# Debugger_V1_1.net
KiCad netlist of a schematic drawn in EAGLE
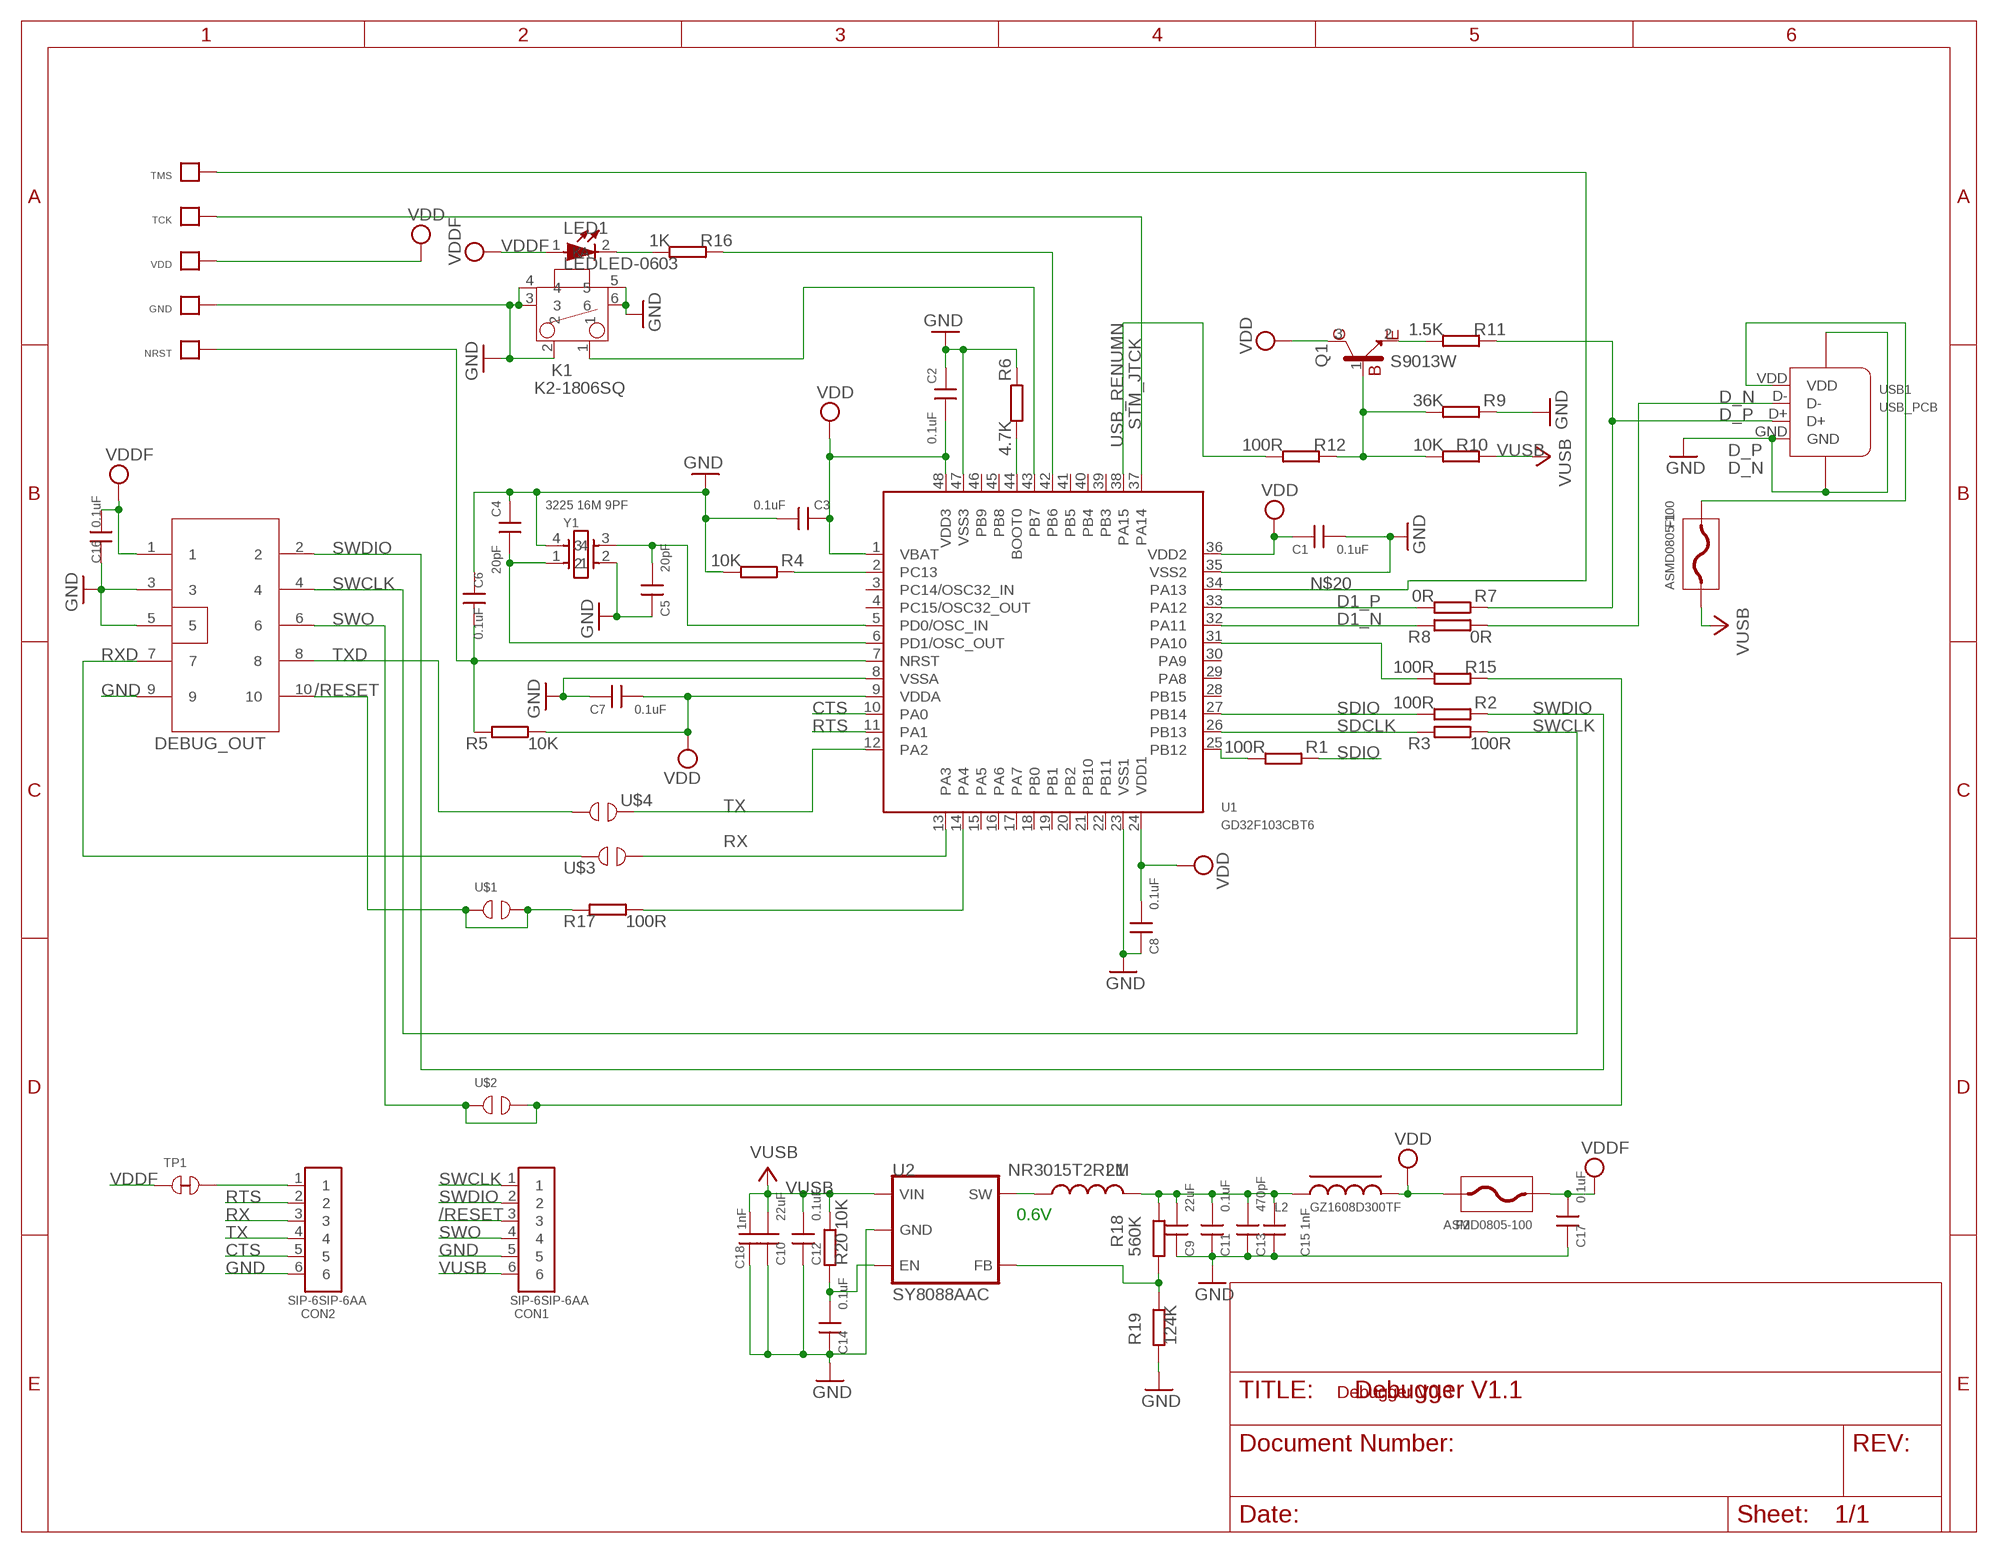
[diagram p0: schematic, sheet 1]

(export (version "E")
  (design (tool "Eeschema 10.0.6"))
  (components
    (comp (ref "C1")
      (value "0.1uF")
      (footprint "eagle-import:C0402")
      (libsource (lib "eagle-import") (part "CAP0402A"))
    )
    (comp (ref "C2")
      (value "0.1uF")
      (footprint "eagle-import:C0402")
      (libsource (lib "eagle-import") (part "CAP0402A"))
    )
    (comp (ref "C3")
      (value "0.1uF")
      (footprint "eagle-import:C0402")
      (libsource (lib "eagle-import") (part "CAP0402A"))
    )
    (comp (ref "C4")
      (value "20pF")
      (footprint "eagle-import:C0402")
      (libsource (lib "eagle-import") (part "CAP0402A"))
    )
    (comp (ref "C5")
      (value "20pF")
      (footprint "eagle-import:C0402")
      (libsource (lib "eagle-import") (part "CAP0402A"))
    )
    (comp (ref "C6")
      (value "0.1uF")
      (footprint "eagle-import:C0402")
      (libsource (lib "eagle-import") (part "CAP0402A"))
    )
    (comp (ref "C7")
      (value "0.1uF")
      (footprint "eagle-import:C0402")
      (libsource (lib "eagle-import") (part "CAP0402A"))
    )
    (comp (ref "C8")
      (value "0.1uF")
      (footprint "eagle-import:C0402")
      (libsource (lib "eagle-import") (part "CAP0402A"))
    )
    (comp (ref "C9")
      (value "22uF")
      (footprint "eagle-import:C0805")
      (libsource (lib "eagle-import") (part "CAPC0805"))
    )
    (comp (ref "C10")
      (value "22uF")
      (footprint "eagle-import:C0805")
      (libsource (lib "eagle-import") (part "CAPC0805"))
    )
    (comp (ref "C11")
      (value "0.1uF")
      (footprint "eagle-import:C0402")
      (libsource (lib "eagle-import") (part "CAP0402A"))
    )
    (comp (ref "C12")
      (value "0.1uF")
      (footprint "eagle-import:C0402")
      (libsource (lib "eagle-import") (part "CAP0402A"))
    )
    (comp (ref "C13")
      (value "470pF")
      (footprint "eagle-import:C0402")
      (libsource (lib "eagle-import") (part "CAP0402A"))
    )
    (comp (ref "C14")
      (value "0.1uF")
      (footprint "eagle-import:C0402")
      (libsource (lib "eagle-import") (part "CAP0402A"))
    )
    (comp (ref "C15")
      (value "1nF")
      (footprint "eagle-import:C0402")
      (libsource (lib "eagle-import") (part "CAP0402A"))
    )
    (comp (ref "C16")
      (value "0.1uF")
      (footprint "eagle-import:C0402")
      (libsource (lib "eagle-import") (part "CAP0402A"))
    )
    (comp (ref "C17")
      (value "0.1uF")
      (footprint "eagle-import:C0402")
      (libsource (lib "eagle-import") (part "CAP0402A"))
    )
    (comp (ref "C18")
      (value "1nF")
      (footprint "eagle-import:C0402")
      (libsource (lib "eagle-import") (part "CAP0402A"))
    )
    (comp (ref "CON1")
      (value "SIP-6SIP-6AA")
      (footprint "eagle-import:PAIZHEN6P_2.54AA")
      (libsource (lib "eagle-import") (part "SIP-6SIP-6AA"))
    )
    (comp (ref "CON2")
      (value "SIP-6SIP-6AA")
      (footprint "eagle-import:PAIZHEN6P_2.54AA")
      (libsource (lib "eagle-import") (part "SIP-6SIP-6AA"))
    )
    (comp (ref "DEBUG_OUT")
      (value "CON5X2")
      (footprint "eagle-import:CON5X2_1.27")
      (libsource (lib "eagle-import") (part "CON5X2"))
    )
    (comp (ref "F1")
      (value "ASMD0805-100")
      (footprint "eagle-import:F0805")
      (libsource (lib "eagle-import") (part "FUSE"))
    )
    (comp (ref "F2")
      (value "ASMD0805-100")
      (footprint "eagle-import:F0805")
      (libsource (lib "eagle-import") (part "FUSE"))
    )
    (comp (ref "GND")
      (value "TPTP")
      (footprint "eagle-import:TP")
      (libsource (lib "eagle-import") (part "TPTP"))
    )
    (comp (ref "K1")
      (value "K2-1806SQ")
      (footprint "eagle-import:K2-1806C")
      (libsource (lib "eagle-import") (part "K2-1806C"))
    )
    (comp (ref "L1")
      (value "NR3015T2R2M")
      (footprint "eagle-import:INDUCTOR-NR3015")
      (libsource (lib "eagle-import") (part "INDUCTORB"))
    )
    (comp (ref "L2")
      (value "GZ1608D300TF")
      (footprint "eagle-import:R-0603A")
      (libsource (lib "eagle-import") (part "L"))
    )
    (comp (ref "LED1")
      (value "LEDLED-0603")
      (footprint "eagle-import:LED-0603")
      (libsource (lib "eagle-import") (part "LEDLED-0603"))
    )
    (comp (ref "NRST")
      (value "TPTP")
      (footprint "eagle-import:TP")
      (libsource (lib "eagle-import") (part "TPTP"))
    )
    (comp (ref "Q1")
      (value "S9013W")
      (footprint "eagle-import:SOT-323")
      (libsource (lib "eagle-import") (part "NPNSOT-323"))
    )
    (comp (ref "R1")
      (value "100R")
      (footprint "eagle-import:R-0402S")
      (libsource (lib "eagle-import") (part "RES0402S"))
    )
    (comp (ref "R2")
      (value "100R")
      (footprint "eagle-import:R-0402S")
      (libsource (lib "eagle-import") (part "RES0402S"))
    )
    (comp (ref "R3")
      (value "100R")
      (footprint "eagle-import:R-0402S")
      (libsource (lib "eagle-import") (part "RES0402S"))
    )
    (comp (ref "R4")
      (value "10K")
      (footprint "eagle-import:R-0402S")
      (libsource (lib "eagle-import") (part "RES0402S"))
    )
    (comp (ref "R5")
      (value "10K")
      (footprint "eagle-import:R-0402S")
      (libsource (lib "eagle-import") (part "RES0402S"))
    )
    (comp (ref "R6")
      (value "4.7K")
      (footprint "eagle-import:R-0402S")
      (libsource (lib "eagle-import") (part "RES0402S"))
    )
    (comp (ref "R7")
      (value "0R")
      (footprint "eagle-import:R-0402S")
      (libsource (lib "eagle-import") (part "RES0402S"))
    )
    (comp (ref "R8")
      (value "0R")
      (footprint "eagle-import:R-0402S")
      (libsource (lib "eagle-import") (part "RES0402S"))
    )
    (comp (ref "R9")
      (value "36K")
      (footprint "eagle-import:R-0402S")
      (libsource (lib "eagle-import") (part "RES0402S"))
    )
    (comp (ref "R10")
      (value "10K")
      (footprint "eagle-import:R-0402S")
      (libsource (lib "eagle-import") (part "RES0402S"))
    )
    (comp (ref "R11")
      (value "1.5K")
      (footprint "eagle-import:R-0402S")
      (libsource (lib "eagle-import") (part "RES0402S"))
    )
    (comp (ref "R12")
      (value "100R")
      (footprint "eagle-import:R-0402S")
      (libsource (lib "eagle-import") (part "RES0402S"))
    )
    (comp (ref "R15")
      (value "100R")
      (footprint "eagle-import:R-0402S")
      (libsource (lib "eagle-import") (part "RES0402S"))
    )
    (comp (ref "R16")
      (value "1K")
      (footprint "eagle-import:R-0402S")
      (libsource (lib "eagle-import") (part "RES0402S"))
    )
    (comp (ref "R17")
      (value "100R")
      (footprint "eagle-import:R-0402S")
      (libsource (lib "eagle-import") (part "RES0402S"))
    )
    (comp (ref "R18")
      (value "560K")
      (footprint "eagle-import:R-0402S")
      (libsource (lib "eagle-import") (part "RES0402S"))
    )
    (comp (ref "R19")
      (value "124K")
      (footprint "eagle-import:R-0402S")
      (libsource (lib "eagle-import") (part "RES0402S"))
    )
    (comp (ref "R20")
      (value "10K")
      (footprint "eagle-import:R-0402S")
      (libsource (lib "eagle-import") (part "RES0402S"))
    )
    (comp (ref "TCK")
      (value "TPTP")
      (footprint "eagle-import:TP")
      (libsource (lib "eagle-import") (part "TPTP"))
    )
    (comp (ref "TMS")
      (value "TPTP")
      (footprint "eagle-import:TP")
      (libsource (lib "eagle-import") (part "TPTP"))
    )
    (comp (ref "TP1")
      (value "TP_SHORT")
      (footprint "eagle-import:TP_SHORT")
      (libsource (lib "eagle-import") (part "TP_SHORT"))
    )
    (comp (ref "U$1")
      (value "TP_OPEN")
      (footprint "eagle-import:TP_OPEN")
      (libsource (lib "eagle-import") (part "TP_OPEN"))
    )
    (comp (ref "U$2")
      (value "TP_OPEN")
      (footprint "eagle-import:TP_OPEN")
      (libsource (lib "eagle-import") (part "TP_OPEN"))
    )
    (comp (ref "U$3")
      (value "TP_OPEN")
      (footprint "eagle-import:TP_OPEN")
      (libsource (lib "eagle-import") (part "TP_OPEN"))
    )
    (comp (ref "U$4")
      (value "TP_OPEN")
      (footprint "eagle-import:TP_OPEN")
      (libsource (lib "eagle-import") (part "TP_OPEN"))
    )
    (comp (ref "U1")
      (value "GD32F103CBT6")
      (footprint "eagle-import:LQFP-48-7X7")
      (libsource (lib "eagle-import") (part "STM32F103LQFP48"))
    )
    (comp (ref "U2")
      (value "SY8088AAC")
      (footprint "eagle-import:SOT23-5L")
      (libsource (lib "eagle-import") (part "AX3701ABA"))
    )
    (comp (ref "USB1")
      (value "USB_PCB")
      (footprint "eagle-import:USB_PCB")
      (libsource (lib "eagle-import") (part "USB_PCB"))
    )
    (comp (ref "VDD")
      (value "TPTP")
      (footprint "eagle-import:TP")
      (libsource (lib "eagle-import") (part "TPTP"))
    )
    (comp (ref "Y1")
      (value "3225 16M 9PF")
      (footprint "eagle-import:CRY_3225_SMT")
      (libsource (lib "eagle-import") (part "CRY-3225CRY-3225"))
    )
  )
  (nets
    (net (code "1") (name "/CTS") (class "Default")
      (node (ref "CON2") (pin "5") (pinfunction "5_5") (pintype "bidirectional"))
      (node (ref "U1") (pin "10") (pinfunction "PA0_10") (pintype "bidirectional"))
    )
    (net (code "2") (name "/D1_N") (class "Default")
      (node (ref "R8") (pin "1") (pinfunction "1_1") (pintype "bidirectional"))
      (node (ref "U1") (pin "32") (pinfunction "PA11_32") (pintype "bidirectional"))
    )
    (net (code "3") (name "/D1_P") (class "Default")
      (node (ref "R7") (pin "2") (pinfunction "2_2") (pintype "bidirectional"))
      (node (ref "U1") (pin "33") (pinfunction "PA12_33") (pintype "bidirectional"))
    )
    (net (code "4") (name "/D_N") (class "Default")
      (node (ref "R8") (pin "2") (pinfunction "2_2") (pintype "bidirectional"))
      (node (ref "USB1") (pin "D-") (pinfunction "D-_D-") (pintype "bidirectional"))
    )
    (net (code "5") (name "/D_P") (class "Default")
      (node (ref "R11") (pin "1") (pinfunction "1_1") (pintype "bidirectional"))
      (node (ref "R7") (pin "1") (pinfunction "1_1") (pintype "bidirectional"))
      (node (ref "USB1") (pin "D+") (pinfunction "D+_D+") (pintype "bidirectional"))
    )
    (net (code "6") (name "/N$20") (class "Default")
      (node (ref "TMS") (pin "P$1") (pinfunction "1_P$1") (pintype "bidirectional"))
      (node (ref "U1") (pin "34") (pinfunction "PA13_34") (pintype "bidirectional"))
    )
    (net (code "7") (name "/RTS") (class "Default")
      (node (ref "CON2") (pin "2") (pinfunction "2_2") (pintype "bidirectional"))
      (node (ref "U1") (pin "11") (pinfunction "PA1_11") (pintype "bidirectional"))
    )
    (net (code "8") (name "/RX") (class "Default")
      (node (ref "CON2") (pin "3") (pinfunction "3_3") (pintype "bidirectional"))
      (node (ref "U$3") (pin "2") (pinfunction "2_2") (pintype "bidirectional"))
      (node (ref "U1") (pin "13") (pinfunction "PA3_13") (pintype "bidirectional"))
    )
    (net (code "9") (name "/RXD") (class "Default")
      (node (ref "DEBUG_OUT") (pin "7") (pinfunction "7_7") (pintype "bidirectional"))
      (node (ref "U$3") (pin "1") (pinfunction "1_1") (pintype "bidirectional"))
    )
    (net (code "10") (name "/SDCLK") (class "Default")
      (node (ref "R3") (pin "1") (pinfunction "1_1") (pintype "bidirectional"))
      (node (ref "U1") (pin "26") (pinfunction "PB13_26") (pintype "bidirectional"))
    )
    (net (code "11") (name "/SDIO") (class "Default")
      (node (ref "R1") (pin "1") (pinfunction "1_1") (pintype "bidirectional"))
      (node (ref "R2") (pin "2") (pinfunction "2_2") (pintype "bidirectional"))
      (node (ref "U1") (pin "27") (pinfunction "PB14_27") (pintype "bidirectional"))
    )
    (net (code "12") (name "/STM_JTCK") (class "Default")
      (node (ref "TCK") (pin "P$1") (pinfunction "1_P$1") (pintype "bidirectional"))
      (node (ref "U1") (pin "37") (pinfunction "PA14_37") (pintype "bidirectional"))
    )
    (net (code "13") (name "/SWCLK") (class "Default")
      (node (ref "CON1") (pin "1") (pinfunction "1_1") (pintype "bidirectional"))
      (node (ref "DEBUG_OUT") (pin "4") (pinfunction "4_4") (pintype "bidirectional"))
      (node (ref "R3") (pin "2") (pinfunction "2_2") (pintype "bidirectional"))
    )
    (net (code "14") (name "/SWDIO") (class "Default")
      (node (ref "CON1") (pin "2") (pinfunction "2_2") (pintype "bidirectional"))
      (node (ref "DEBUG_OUT") (pin "2") (pinfunction "2_2") (pintype "bidirectional"))
      (node (ref "R2") (pin "1") (pinfunction "1_1") (pintype "bidirectional"))
    )
    (net (code "15") (name "/SWO") (class "Default")
      (node (ref "CON1") (pin "4") (pinfunction "4_4") (pintype "bidirectional"))
      (node (ref "DEBUG_OUT") (pin "6") (pinfunction "6_6") (pintype "bidirectional"))
      (node (ref "R15") (pin "1") (pinfunction "1_1") (pintype "bidirectional"))
      (node (ref "U$2") (pin "1") (pinfunction "1_1") (pintype "bidirectional"))
      (node (ref "U$2") (pin "2") (pinfunction "2_2") (pintype "bidirectional"))
    )
    (net (code "16") (name "/TX") (class "Default")
      (node (ref "CON2") (pin "4") (pinfunction "4_4") (pintype "bidirectional"))
      (node (ref "U$4") (pin "1") (pinfunction "1_1") (pintype "bidirectional"))
      (node (ref "U1") (pin "12") (pinfunction "PA2_12") (pintype "bidirectional"))
    )
    (net (code "17") (name "/TXD") (class "Default")
      (node (ref "DEBUG_OUT") (pin "8") (pinfunction "8_8") (pintype "bidirectional"))
      (node (ref "U$4") (pin "2") (pinfunction "2_2") (pintype "bidirectional"))
    )
    (net (code "18") (name "/USB_RENUMN") (class "Default")
      (node (ref "R12") (pin "2") (pinfunction "2_2") (pintype "bidirectional"))
      (node (ref "U1") (pin "38") (pinfunction "PA15_38") (pintype "bidirectional"))
    )
    (net (code "19") (name "/{slash}RESET") (class "Default")
      (node (ref "CON1") (pin "3") (pinfunction "3_3") (pintype "bidirectional"))
      (node (ref "DEBUG_OUT") (pin "10") (pinfunction "10_10") (pintype "bidirectional"))
      (node (ref "R17") (pin "1") (pinfunction "1_1") (pintype "bidirectional"))
      (node (ref "U$1") (pin "1") (pinfunction "1_1") (pintype "bidirectional"))
      (node (ref "U$1") (pin "2") (pinfunction "2_2") (pintype "bidirectional"))
    )
    (net (code "20") (name "GND") (class "Default")
      (node (ref "C1") (pin "1") (pinfunction "1_1") (pintype "bidirectional"))
      (node (ref "C10") (pin "2") (pinfunction "2_2") (pintype "bidirectional"))
      (node (ref "C11") (pin "2") (pinfunction "2_2") (pintype "bidirectional"))
      (node (ref "C12") (pin "2") (pinfunction "2_2") (pintype "bidirectional"))
      (node (ref "C13") (pin "2") (pinfunction "2_2") (pintype "bidirectional"))
      (node (ref "C14") (pin "2") (pinfunction "2_2") (pintype "bidirectional"))
      (node (ref "C15") (pin "2") (pinfunction "2_2") (pintype "bidirectional"))
      (node (ref "C16") (pin "2") (pinfunction "2_2") (pintype "bidirectional"))
      (node (ref "C17") (pin "2") (pinfunction "2_2") (pintype "bidirectional"))
      (node (ref "C18") (pin "2") (pinfunction "2_2") (pintype "bidirectional"))
      (node (ref "C2") (pin "2") (pinfunction "2_2") (pintype "bidirectional"))
      (node (ref "C3") (pin "1") (pinfunction "1_1") (pintype "bidirectional"))
      (node (ref "C4") (pin "2") (pinfunction "2_2") (pintype "bidirectional"))
      (node (ref "C5") (pin "2") (pinfunction "2_2") (pintype "bidirectional"))
      (node (ref "C6") (pin "2") (pinfunction "2_2") (pintype "bidirectional"))
      (node (ref "C7") (pin "2") (pinfunction "2_2") (pintype "bidirectional"))
      (node (ref "C8") (pin "2") (pinfunction "2_2") (pintype "bidirectional"))
      (node (ref "C9") (pin "2") (pinfunction "2_2") (pintype "bidirectional"))
      (node (ref "CON1") (pin "5") (pinfunction "5_5") (pintype "bidirectional"))
      (node (ref "CON2") (pin "6") (pinfunction "6_6") (pintype "bidirectional"))
      (node (ref "DEBUG_OUT") (pin "3") (pinfunction "3_3") (pintype "bidirectional"))
      (node (ref "DEBUG_OUT") (pin "5") (pinfunction "5_5") (pintype "bidirectional"))
      (node (ref "DEBUG_OUT") (pin "9") (pinfunction "9_9") (pintype "bidirectional"))
      (node (ref "GND") (pin "P$1") (pinfunction "1_P$1") (pintype "bidirectional"))
      (node (ref "K1") (pin "2") (pinfunction "2_2") (pintype "bidirectional"))
      (node (ref "K1") (pin "3") (pinfunction "3_3") (pintype "bidirectional"))
      (node (ref "K1") (pin "4") (pinfunction "4_4") (pintype "bidirectional"))
      (node (ref "K1") (pin "5") (pinfunction "5_5") (pintype "bidirectional"))
      (node (ref "K1") (pin "6") (pinfunction "6_6") (pintype "bidirectional"))
      (node (ref "R19") (pin "1") (pinfunction "1_1") (pintype "bidirectional"))
      (node (ref "R4") (pin "2") (pinfunction "2_2") (pintype "bidirectional"))
      (node (ref "R6") (pin "1") (pinfunction "1_1") (pintype "bidirectional"))
      (node (ref "R9") (pin "1") (pinfunction "1_1") (pintype "bidirectional"))
      (node (ref "U1") (pin "23") (pinfunction "VSS1_23") (pintype "bidirectional"))
      (node (ref "U1") (pin "35") (pinfunction "VSS2_35") (pintype "bidirectional"))
      (node (ref "U1") (pin "47") (pinfunction "VSS3_47") (pintype "bidirectional"))
      (node (ref "U1") (pin "8") (pinfunction "VSSA_8") (pintype "bidirectional"))
      (node (ref "U2") (pin "2") (pinfunction "GND_2") (pintype "power_in"))
      (node (ref "USB1") (pin "GND") (pinfunction "GND_GND") (pintype "bidirectional"))
      (node (ref "USB1") (pin "GND1") (pinfunction "GND1_GND1") (pintype "power_in"))
      (node (ref "USB1") (pin "GND2") (pinfunction "GND2_GND2") (pintype "bidirectional"))
      (node (ref "Y1") (pin "2") (pinfunction "2_2") (pintype "bidirectional"))
      (node (ref "Y1") (pin "4") (pinfunction "4_4") (pintype "bidirectional"))
    )
    (net (code "21") (name "Net-(C11-Pad1)") (class "Default")
      (node (ref "C11") (pin "1") (pinfunction "1_1") (pintype "bidirectional"))
      (node (ref "C13") (pin "1") (pinfunction "1_1") (pintype "bidirectional"))
      (node (ref "C15") (pin "1") (pinfunction "1_1") (pintype "bidirectional"))
      (node (ref "C9") (pin "1") (pinfunction "1_1") (pintype "bidirectional"))
      (node (ref "L1") (pin "2") (pinfunction "2_2") (pintype "passive"))
      (node (ref "L2") (pin "1") (pinfunction "1_1") (pintype "bidirectional"))
      (node (ref "R18") (pin "2") (pinfunction "2_2") (pintype "bidirectional"))
    )
    (net (code "22") (name "Net-(F1-2)") (class "Default")
      (node (ref "F1") (pin "P$2") (pinfunction "2_P$2") (pintype "bidirectional"))
      (node (ref "USB1") (pin "VDD") (pinfunction "VDD_VDD") (pintype "bidirectional"))
    )
    (net (code "23") (name "Net-(LED1-K)") (class "Default")
      (node (ref "LED1") (pin "2") (pinfunction "K_2") (pintype "bidirectional"))
      (node (ref "R16") (pin "2") (pinfunction "2_2") (pintype "bidirectional"))
    )
    (net (code "24") (name "Net-(NRST-1)") (class "Default")
      (node (ref "C6") (pin "1") (pinfunction "1_1") (pintype "bidirectional"))
      (node (ref "NRST") (pin "P$1") (pinfunction "1_P$1") (pintype "bidirectional"))
      (node (ref "R5") (pin "1") (pinfunction "1_1") (pintype "bidirectional"))
      (node (ref "U1") (pin "7") (pinfunction "NRST_7") (pintype "bidirectional"))
    )
    (net (code "25") (name "Net-(Q1-B)") (class "Default")
      (node (ref "Q1") (pin "1") (pinfunction "B_1") (pintype "bidirectional"))
      (node (ref "R10") (pin "2") (pinfunction "2_2") (pintype "bidirectional"))
      (node (ref "R12") (pin "1") (pinfunction "1_1") (pintype "bidirectional"))
      (node (ref "R9") (pin "2") (pinfunction "2_2") (pintype "bidirectional"))
    )
    (net (code "26") (name "Net-(Q1-E)") (class "Default")
      (node (ref "Q1") (pin "2") (pinfunction "E_2") (pintype "bidirectional"))
      (node (ref "R11") (pin "2") (pinfunction "2_2") (pintype "bidirectional"))
    )
    (net (code "27") (name "Net-(U1-BOOT0)") (class "Default")
      (node (ref "R6") (pin "2") (pinfunction "2_2") (pintype "bidirectional"))
      (node (ref "U1") (pin "44") (pinfunction "BOOT0_44") (pintype "bidirectional"))
    )
    (net (code "28") (name "Net-(U1-PA4)") (class "Default")
      (node (ref "R17") (pin "2") (pinfunction "2_2") (pintype "bidirectional"))
      (node (ref "U1") (pin "14") (pinfunction "PA4_14") (pintype "bidirectional"))
    )
    (net (code "29") (name "Net-(U1-PA10)") (class "Default")
      (node (ref "R15") (pin "2") (pinfunction "2_2") (pintype "bidirectional"))
      (node (ref "U1") (pin "31") (pinfunction "PA10_31") (pintype "bidirectional"))
    )
    (net (code "30") (name "Net-(U1-PB6)") (class "Default")
      (node (ref "R16") (pin "1") (pinfunction "1_1") (pintype "bidirectional"))
      (node (ref "U1") (pin "42") (pinfunction "PB6_42") (pintype "bidirectional"))
    )
    (net (code "31") (name "Net-(U1-PB7)") (class "Default")
      (node (ref "K1") (pin "1") (pinfunction "1_1") (pintype "bidirectional"))
      (node (ref "U1") (pin "43") (pinfunction "PB7_43") (pintype "bidirectional"))
    )
    (net (code "32") (name "Net-(U1-PB12)") (class "Default")
      (node (ref "R1") (pin "2") (pinfunction "2_2") (pintype "bidirectional"))
      (node (ref "U1") (pin "25") (pinfunction "PB12_25") (pintype "bidirectional"))
    )
    (net (code "33") (name "Net-(U1-PC13)") (class "Default")
      (node (ref "R4") (pin "1") (pinfunction "1_1") (pintype "bidirectional"))
      (node (ref "U1") (pin "2") (pinfunction "PC13_2") (pintype "bidirectional"))
    )
    (net (code "34") (name "Net-(U1-PD0{slash}OSC_IN)") (class "Default")
      (node (ref "C5") (pin "1") (pinfunction "1_1") (pintype "bidirectional"))
      (node (ref "U1") (pin "5") (pinfunction "PD0/OSC_IN_5") (pintype "bidirectional"))
      (node (ref "Y1") (pin "3") (pinfunction "3_3") (pintype "bidirectional"))
    )
    (net (code "35") (name "Net-(U1-PD1{slash}OSC_OUT)") (class "Default")
      (node (ref "C4") (pin "1") (pinfunction "1_1") (pintype "bidirectional"))
      (node (ref "U1") (pin "6") (pinfunction "PD1/OSC_OUT_6") (pintype "bidirectional"))
      (node (ref "Y1") (pin "1") (pinfunction "1_1") (pintype "bidirectional"))
    )
    (net (code "36") (name "Net-(U2-EN)") (class "Default")
      (node (ref "C14") (pin "1") (pinfunction "1_1") (pintype "bidirectional"))
      (node (ref "R20") (pin "1") (pinfunction "1_1") (pintype "bidirectional"))
      (node (ref "U2") (pin "1") (pinfunction "EN_1") (pintype "input"))
    )
    (net (code "37") (name "Net-(U2-FB)") (class "Default")
      (node (ref "R18") (pin "1") (pinfunction "1_1") (pintype "bidirectional"))
      (node (ref "R19") (pin "2") (pinfunction "2_2") (pintype "bidirectional"))
      (node (ref "U2") (pin "5") (pinfunction "FB_5") (pintype "input"))
    )
    (net (code "38") (name "Net-(U2-SW)") (class "Default")
      (node (ref "L1") (pin "1") (pinfunction "1_1") (pintype "passive"))
      (node (ref "U2") (pin "3") (pinfunction "SW_3") (pintype "output"))
    )
    (net (code "39") (name "VDD") (class "Default")
      (node (ref "C1") (pin "2") (pinfunction "2_2") (pintype "bidirectional"))
      (node (ref "C2") (pin "1") (pinfunction "1_1") (pintype "bidirectional"))
      (node (ref "C3") (pin "2") (pinfunction "2_2") (pintype "bidirectional"))
      (node (ref "C7") (pin "1") (pinfunction "1_1") (pintype "bidirectional"))
      (node (ref "C8") (pin "1") (pinfunction "1_1") (pintype "bidirectional"))
      (node (ref "F2") (pin "P$2") (pinfunction "2_P$2") (pintype "bidirectional"))
      (node (ref "L2") (pin "2") (pinfunction "2_2") (pintype "bidirectional"))
      (node (ref "Q1") (pin "3") (pinfunction "C_3") (pintype "bidirectional"))
      (node (ref "R5") (pin "2") (pinfunction "2_2") (pintype "bidirectional"))
      (node (ref "U1") (pin "1") (pinfunction "VBAT_1") (pintype "bidirectional"))
      (node (ref "U1") (pin "24") (pinfunction "VDD1_24") (pintype "bidirectional"))
      (node (ref "U1") (pin "36") (pinfunction "VDD2_36") (pintype "bidirectional"))
      (node (ref "U1") (pin "48") (pinfunction "VDD3_48") (pintype "bidirectional"))
      (node (ref "U1") (pin "9") (pinfunction "VDDA_9") (pintype "bidirectional"))
      (node (ref "VDD") (pin "P$1") (pinfunction "1_P$1") (pintype "bidirectional"))
    )
    (net (code "40") (name "VDDF") (class "Default")
      (node (ref "C16") (pin "1") (pinfunction "1_1") (pintype "bidirectional"))
      (node (ref "C17") (pin "1") (pinfunction "1_1") (pintype "bidirectional"))
      (node (ref "CON2") (pin "1") (pinfunction "1_1") (pintype "bidirectional"))
      (node (ref "DEBUG_OUT") (pin "1") (pinfunction "1_1") (pintype "bidirectional"))
      (node (ref "F2") (pin "P$1") (pinfunction "1_P$1") (pintype "bidirectional"))
      (node (ref "LED1") (pin "1") (pinfunction "A_1") (pintype "bidirectional"))
      (node (ref "TP1") (pin "1") (pinfunction "1_1") (pintype "bidirectional"))
      (node (ref "TP1") (pin "2") (pinfunction "2_2") (pintype "bidirectional"))
    )
    (net (code "41") (name "VUSB") (class "Default")
      (node (ref "C10") (pin "1") (pinfunction "1_1") (pintype "bidirectional"))
      (node (ref "C12") (pin "1") (pinfunction "1_1") (pintype "bidirectional"))
      (node (ref "C18") (pin "1") (pinfunction "1_1") (pintype "bidirectional"))
      (node (ref "CON1") (pin "6") (pinfunction "6_6") (pintype "bidirectional"))
      (node (ref "F1") (pin "P$1") (pinfunction "1_P$1") (pintype "bidirectional"))
      (node (ref "R10") (pin "1") (pinfunction "1_1") (pintype "bidirectional"))
      (node (ref "R20") (pin "2") (pinfunction "2_2") (pintype "bidirectional"))
      (node (ref "U2") (pin "4") (pinfunction "VIN_4") (pintype "input"))
    )
    (net (code "42") (name "unconnected-(U1-PA5-Pad15)") (class "Default")
      (node (ref "U1") (pin "15") (pinfunction "PA5_15") (pintype "bidirectional"))
    )
    (net (code "43") (name "unconnected-(U1-PA6-Pad16)") (class "Default")
      (node (ref "U1") (pin "16") (pinfunction "PA6_16") (pintype "bidirectional"))
    )
    (net (code "44") (name "unconnected-(U1-PA7-Pad17)") (class "Default")
      (node (ref "U1") (pin "17") (pinfunction "PA7_17") (pintype "bidirectional"))
    )
    (net (code "45") (name "unconnected-(U1-PA8-Pad29)") (class "Default")
      (node (ref "U1") (pin "29") (pinfunction "PA8_29") (pintype "bidirectional"))
    )
    (net (code "46") (name "unconnected-(U1-PA9-Pad30)") (class "Default")
      (node (ref "U1") (pin "30") (pinfunction "PA9_30") (pintype "bidirectional"))
    )
    (net (code "47") (name "unconnected-(U1-PB0-Pad18)") (class "Default")
      (node (ref "U1") (pin "18") (pinfunction "PB0_18") (pintype "bidirectional"))
    )
    (net (code "48") (name "unconnected-(U1-PB1-Pad19)") (class "Default")
      (node (ref "U1") (pin "19") (pinfunction "PB1_19") (pintype "bidirectional"))
    )
    (net (code "49") (name "unconnected-(U1-PB2-Pad20)") (class "Default")
      (node (ref "U1") (pin "20") (pinfunction "PB2_20") (pintype "bidirectional"))
    )
    (net (code "50") (name "unconnected-(U1-PB3-Pad39)") (class "Default")
      (node (ref "U1") (pin "39") (pinfunction "PB3_39") (pintype "bidirectional"))
    )
    (net (code "51") (name "unconnected-(U1-PB4-Pad40)") (class "Default")
      (node (ref "U1") (pin "40") (pinfunction "PB4_40") (pintype "bidirectional"))
    )
    (net (code "52") (name "unconnected-(U1-PB5-Pad41)") (class "Default")
      (node (ref "U1") (pin "41") (pinfunction "PB5_41") (pintype "bidirectional"))
    )
    (net (code "53") (name "unconnected-(U1-PB8-Pad45)") (class "Default")
      (node (ref "U1") (pin "45") (pinfunction "PB8_45") (pintype "bidirectional"))
    )
    (net (code "54") (name "unconnected-(U1-PB9-Pad46)") (class "Default")
      (node (ref "U1") (pin "46") (pinfunction "PB9_46") (pintype "bidirectional"))
    )
    (net (code "55") (name "unconnected-(U1-PB10-Pad21)") (class "Default")
      (node (ref "U1") (pin "21") (pinfunction "PB10_21") (pintype "bidirectional"))
    )
    (net (code "56") (name "unconnected-(U1-PB11-Pad22)") (class "Default")
      (node (ref "U1") (pin "22") (pinfunction "PB11_22") (pintype "bidirectional"))
    )
    (net (code "57") (name "unconnected-(U1-PB15-Pad28)") (class "Default")
      (node (ref "U1") (pin "28") (pinfunction "PB15_28") (pintype "bidirectional"))
    )
    (net (code "58") (name "unconnected-(U1-PC14{slash}OSC32_IN-Pad3)") (class "Default")
      (node (ref "U1") (pin "3") (pinfunction "PC14/OSC32_IN_3") (pintype "bidirectional"))
    )
    (net (code "59") (name "unconnected-(U1-PC15{slash}OSC32_OUT-Pad4)") (class "Default")
      (node (ref "U1") (pin "4") (pinfunction "PC15/OSC32_OUT_4") (pintype "bidirectional"))
    )
  )
)
